# SBM20_counter.net
KiCad netlist of a schematic drawn in EAGLE
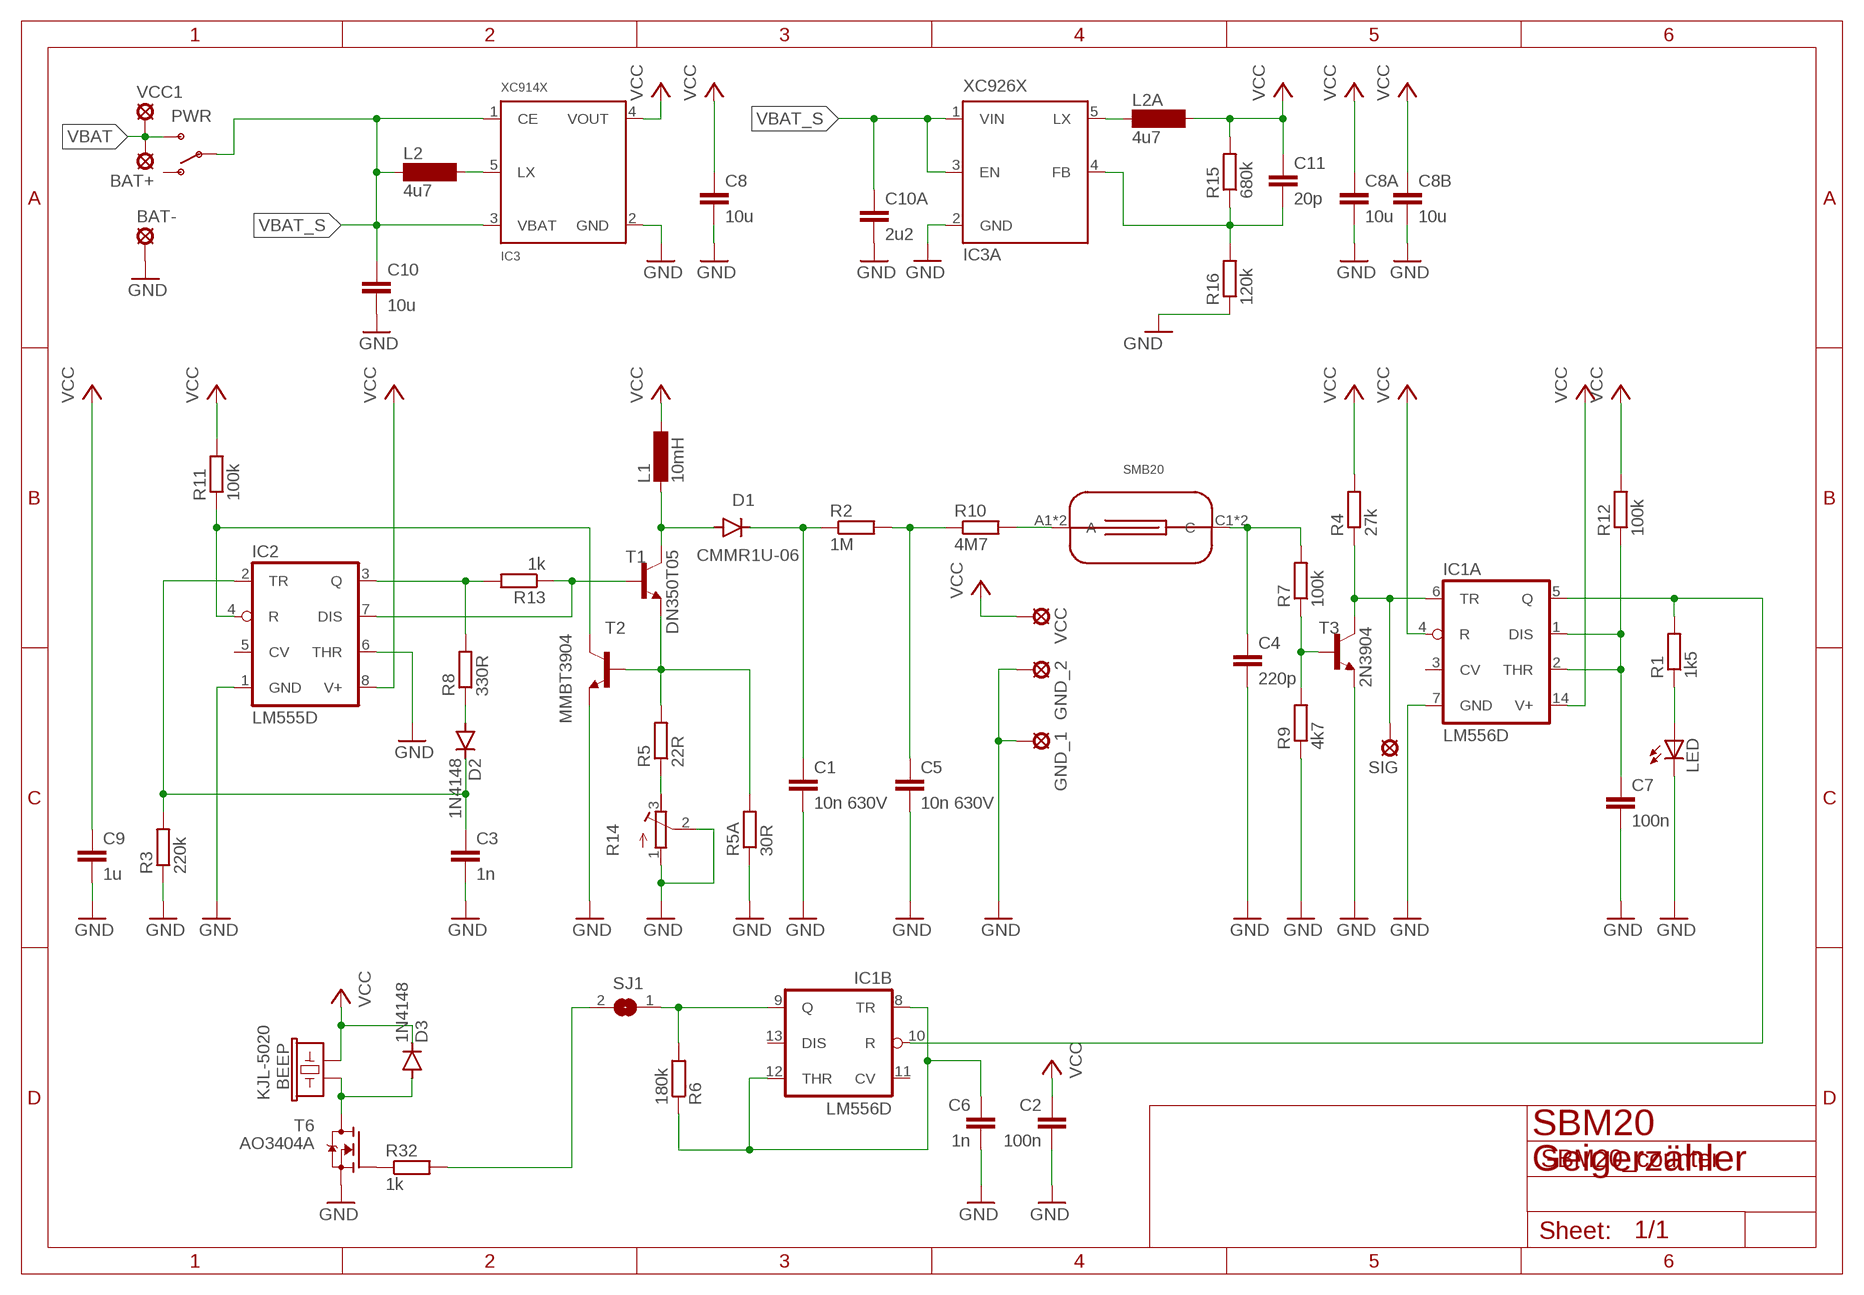
[diagram p0: schematic, sheet 1]

(export (version "E")
  (design (tool "Eeschema 10.0.6"))
  (components
    (comp (ref "BAT+")
      (value "LSP10_CAST")
      (footprint "eagle-import:CASTEL_1")
      (libsource (lib "eagle-import") (part "LSP10_CAST"))
    )
    (comp (ref "BAT-")
      (value "LSP10_CAST")
      (footprint "eagle-import:CASTEL_1")
      (libsource (lib "eagle-import") (part "LSP10_CAST"))
    )
    (comp (ref "BEEP")
      (value "KJL-5020")
      (footprint "eagle-import:KLJ-5020")
      (libsource (lib "eagle-import") (part "BUZZER-5020"))
    )
    (comp (ref "C1")
      (value "10n 630V")
      (footprint "eagle-import:C1206")
      (libsource (lib "eagle-import") (part "C-EUC1206"))
    )
    (comp (ref "C2")
      (value "100n")
      (footprint "eagle-import:C0603")
      (libsource (lib "eagle-import") (part "C-EUC0603"))
    )
    (comp (ref "C3")
      (value "1n")
      (footprint "eagle-import:C0603")
      (libsource (lib "eagle-import") (part "C-EUC0603"))
    )
    (comp (ref "C4")
      (value "220p")
      (footprint "eagle-import:C0603")
      (libsource (lib "eagle-import") (part "C-EUC0603"))
    )
    (comp (ref "C5")
      (value "10n 630V")
      (footprint "eagle-import:C1206")
      (libsource (lib "eagle-import") (part "C-EUC1206"))
    )
    (comp (ref "C6")
      (value "1n")
      (footprint "eagle-import:C0603")
      (libsource (lib "eagle-import") (part "C-EUC0603"))
    )
    (comp (ref "C7")
      (value "100n")
      (footprint "eagle-import:C0603")
      (libsource (lib "eagle-import") (part "C-EUC0603"))
    )
    (comp (ref "C8")
      (value "10u")
      (footprint "eagle-import:C1206")
      (libsource (lib "eagle-import") (part "C-EUC1206"))
    )
    (comp (ref "C8A")
      (value "10u")
      (footprint "eagle-import:C1206")
      (libsource (lib "eagle-import") (part "C-EUC1206"))
    )
    (comp (ref "C8B")
      (value "10u")
      (footprint "eagle-import:C1206")
      (libsource (lib "eagle-import") (part "C-EUC1206"))
    )
    (comp (ref "C9")
      (value "1u")
      (footprint "eagle-import:C1206")
      (libsource (lib "eagle-import") (part "C-EUC1206"))
    )
    (comp (ref "C10")
      (value "10u")
      (footprint "eagle-import:C1206")
      (libsource (lib "eagle-import") (part "C-EUC1206"))
    )
    (comp (ref "C10A")
      (value "2u2")
      (footprint "eagle-import:C1206")
      (libsource (lib "eagle-import") (part "C-EUC1206"))
    )
    (comp (ref "C11")
      (value "20p")
      (footprint "eagle-import:C0603")
      (libsource (lib "eagle-import") (part "C-EUC0603"))
    )
    (comp (ref "D1")
      (value "CMMR1U-06")
      (footprint "eagle-import:DO-214AC")
      (libsource (lib "eagle-import") (part "DIODE-DO-214AC"))
    )
    (comp (ref "D2")
      (value "1N4148")
      (footprint "eagle-import:SOD123")
      (libsource (lib "eagle-import") (part "DIODE-SOD123"))
    )
    (comp (ref "D3")
      (value "1N4148")
      (footprint "eagle-import:SOD123")
      (libsource (lib "eagle-import") (part "DIODE-SOD123"))
    )
    (comp (ref "GND_1")
      (value "LSP10_CAST")
      (footprint "eagle-import:CASTEL_1")
      (libsource (lib "eagle-import") (part "LSP10_CAST"))
    )
    (comp (ref "GND_2")
      (value "LSP10_CAST")
      (footprint "eagle-import:CASTEL_1")
      (libsource (lib "eagle-import") (part "LSP10_CAST"))
    )
    (comp (ref "IC1")
      (value "LM556D")
      (footprint "eagle-import:SO14")
      (libsource (lib "eagle-import") (part "556DLM"))
    )
    (comp (ref "IC2")
      (value "LM555D")
      (footprint "eagle-import:SO08")
      (libsource (lib "eagle-import") (part "555DLM"))
    )
    (comp (ref "IC3")
      (value "XC914X")
      (footprint "eagle-import:SOT23-5")
      (libsource (lib "eagle-import") (part "XC914X"))
    )
    (comp (ref "IC3A")
      (value "XC926X")
      (footprint "eagle-import:SOT23-5")
      (libsource (lib "eagle-import") (part "XC926X"))
    )
    (comp (ref "L1")
      (value "10mH")
      (footprint "eagle-import:L8065")
      (libsource (lib "eagle-import") (part "L-EUL8065"))
    )
    (comp (ref "L2")
      (value "4u7")
      (footprint "eagle-import:L5050")
      (libsource (lib "eagle-import") (part "L"))
    )
    (comp (ref "L2A")
      (value "4u7")
      (footprint "eagle-import:L5050")
      (libsource (lib "eagle-import") (part "L"))
    )
    (comp (ref "LED")
      (value "LEDCHIPLED_1206")
      (footprint "eagle-import:CHIPLED_1206")
      (libsource (lib "eagle-import") (part "LEDCHIPLED_1206"))
    )
    (comp (ref "PWR")
      (value "SWITCH-SPDT-SMD-A")
      (footprint "eagle-import:SWITCH-SPST-SMD-A")
      (libsource (lib "eagle-import") (part "SWITCH-SPDT-SMD-A"))
    )
    (comp (ref "R1")
      (value "1k5")
      (footprint "eagle-import:R0603")
      (libsource (lib "eagle-import") (part "R-EU_R0603"))
    )
    (comp (ref "R2")
      (value "1M")
      (footprint "eagle-import:R1206")
      (libsource (lib "eagle-import") (part "R-EU_R1206"))
    )
    (comp (ref "R3")
      (value "220k")
      (footprint "eagle-import:R0603")
      (libsource (lib "eagle-import") (part "R-EU_R0603"))
    )
    (comp (ref "R4")
      (value "27k")
      (footprint "eagle-import:R0603")
      (libsource (lib "eagle-import") (part "R-EU_R0603"))
    )
    (comp (ref "R5")
      (value "22R")
      (footprint "eagle-import:R0603")
      (libsource (lib "eagle-import") (part "R-EU_R0603"))
    )
    (comp (ref "R5A")
      (value "30R")
      (footprint "eagle-import:R0603")
      (libsource (lib "eagle-import") (part "R-EU_R0603"))
    )
    (comp (ref "R6")
      (value "180k")
      (footprint "eagle-import:R0603")
      (libsource (lib "eagle-import") (part "R-EU_R0603"))
    )
    (comp (ref "R7")
      (value "100k")
      (footprint "eagle-import:R0603")
      (libsource (lib "eagle-import") (part "R-EU_R0603"))
    )
    (comp (ref "R8")
      (value "330R")
      (footprint "eagle-import:R0603")
      (libsource (lib "eagle-import") (part "R-EU_R0603"))
    )
    (comp (ref "R9")
      (value "4k7")
      (footprint "eagle-import:R0603")
      (libsource (lib "eagle-import") (part "R-EU_R0603"))
    )
    (comp (ref "R10")
      (value "4M7")
      (footprint "eagle-import:R1206")
      (libsource (lib "eagle-import") (part "R-EU_R1206"))
    )
    (comp (ref "R11")
      (value "100k")
      (footprint "eagle-import:R0603")
      (libsource (lib "eagle-import") (part "R-EU_R0603"))
    )
    (comp (ref "R12")
      (value "100k")
      (footprint "eagle-import:R0603")
      (libsource (lib "eagle-import") (part "R-EU_R0603"))
    )
    (comp (ref "R13")
      (value "1k")
      (footprint "eagle-import:R0603")
      (libsource (lib "eagle-import") (part "R-EU_R0603"))
    )
    (comp (ref "R14")
      (value "R-TRIMM3224J")
      (footprint "eagle-import:RTRIM3224J")
      (libsource (lib "eagle-import") (part "R-TRIMM3224J"))
    )
    (comp (ref "R15")
      (value "680k")
      (footprint "eagle-import:R0603")
      (libsource (lib "eagle-import") (part "R-EU_R0603"))
    )
    (comp (ref "R16")
      (value "120k")
      (footprint "eagle-import:R0603")
      (libsource (lib "eagle-import") (part "R-EU_R0603"))
    )
    (comp (ref "R32")
      (value "1k")
      (footprint "eagle-import:R0603")
      (libsource (lib "eagle-import") (part "R-EU_R0603"))
    )
    (comp (ref "SIG")
      (value "LSP10_CAST")
      (footprint "eagle-import:CASTEL_1")
      (libsource (lib "eagle-import") (part "LSP10_CAST"))
    )
    (comp (ref "SJ1") (value "SJ") (footprint "eagle-import:SJ") (libsource (lib "eagle-import") (part "SJ")))
    (comp (ref "T1")
      (value "DN350T05")
      (footprint "eagle-import:SOT23-BEC")
      (libsource (lib "eagle-import") (part "-NPN-SOT23-BECMMBT3904LT1"))
    )
    (comp (ref "T2")
      (value "MMBT3904")
      (footprint "eagle-import:SOT23-BEC")
      (libsource (lib "eagle-import") (part "-NPN-SOT23-BECMMBT3904LT1"))
    )
    (comp (ref "T3")
      (value "2N3904")
      (footprint "eagle-import:SOT23-BEC")
      (libsource (lib "eagle-import") (part "-NPN-SOT23-BECMMBT3904LT1"))
    )
    (comp (ref "T6")
      (value "AO3404A")
      (footprint "eagle-import:SOT23")
      (libsource (lib "eagle-import") (part "N-MOSFET-SOT23-3"))
    )
    (comp (ref "U$1")
      (value "SMB20")
      (footprint "eagle-import:STS5")
      (libsource (lib "eagle-import") (part "STS5"))
    )
    (comp (ref "VCC")
      (value "LSP10_CAST")
      (footprint "eagle-import:CASTEL_1")
      (libsource (lib "eagle-import") (part "LSP10_CAST"))
    )
    (comp (ref "VCC1")
      (value "LSP10_CAST")
      (footprint "eagle-import:CASTEL_1")
      (libsource (lib "eagle-import") (part "LSP10_CAST"))
    )
  )
  (nets
    (net (code "1") (name "GND") (class "Default")
      (node (ref "BAT-") (pin "C") (pinfunction "MP_C") (pintype "passive"))
      (node (ref "BAT-") (pin "V") (pinfunction "MP_V") (pintype "passive"))
      (node (ref "C1") (pin "2") (pinfunction "2_2") (pintype "passive"))
      (node (ref "C10") (pin "2") (pinfunction "2_2") (pintype "passive"))
      (node (ref "C10A") (pin "2") (pinfunction "2_2") (pintype "passive"))
      (node (ref "C2") (pin "2") (pinfunction "2_2") (pintype "passive"))
      (node (ref "C3") (pin "2") (pinfunction "2_2") (pintype "passive"))
      (node (ref "C4") (pin "2") (pinfunction "2_2") (pintype "passive"))
      (node (ref "C5") (pin "2") (pinfunction "2_2") (pintype "passive"))
      (node (ref "C6") (pin "2") (pinfunction "2_2") (pintype "passive"))
      (node (ref "C7") (pin "2") (pinfunction "2_2") (pintype "passive"))
      (node (ref "C8") (pin "2") (pinfunction "2_2") (pintype "passive"))
      (node (ref "C8A") (pin "2") (pinfunction "2_2") (pintype "passive"))
      (node (ref "C8B") (pin "2") (pinfunction "2_2") (pintype "passive"))
      (node (ref "C9") (pin "2") (pinfunction "2_2") (pintype "passive"))
      (node (ref "GND_1") (pin "C") (pinfunction "MP_C") (pintype "passive"))
      (node (ref "GND_1") (pin "V") (pinfunction "MP_V") (pintype "passive"))
      (node (ref "GND_2") (pin "C") (pinfunction "MP_C") (pintype "passive"))
      (node (ref "GND_2") (pin "V") (pinfunction "MP_V") (pintype "passive"))
      (node (ref "IC1") (pin "7") (pinfunction "GND_7") (pintype "power_in"))
      (node (ref "IC2") (pin "1") (pinfunction "GND_1") (pintype "power_in"))
      (node (ref "IC2") (pin "6") (pinfunction "THR_6") (pintype "input"))
      (node (ref "IC3") (pin "2") (pinfunction "GND_2") (pintype "power_in"))
      (node (ref "IC3A") (pin "2") (pinfunction "GND_2") (pintype "power_in"))
      (node (ref "LED") (pin "C") (pinfunction "C_C") (pintype "passive"))
      (node (ref "R14") (pin "1") (pinfunction "A_1") (pintype "passive"))
      (node (ref "R14") (pin "2") (pinfunction "S_2") (pintype "passive"))
      (node (ref "R16") (pin "1") (pinfunction "1_1") (pintype "passive"))
      (node (ref "R3") (pin "1") (pinfunction "1_1") (pintype "passive"))
      (node (ref "R5A") (pin "1") (pinfunction "1_1") (pintype "passive"))
      (node (ref "R9") (pin "1") (pinfunction "1_1") (pintype "passive"))
      (node (ref "T2") (pin "E") (pinfunction "E_E") (pintype "passive"))
      (node (ref "T3") (pin "E") (pinfunction "E_E") (pintype "passive"))
      (node (ref "T6") (pin "2") (pinfunction "S_2") (pintype "passive"))
    )
    (net (code "2") (name "Net-(BEEP-2)") (class "Default")
      (node (ref "BEEP") (pin "-") (pinfunction "2_-") (pintype "passive"))
      (node (ref "D3") (pin "A") (pinfunction "A_A") (pintype "passive"))
      (node (ref "T6") (pin "3") (pinfunction "D_3") (pintype "passive"))
    )
    (net (code "3") (name "Net-(C1-Pad1)") (class "Default")
      (node (ref "C1") (pin "1") (pinfunction "1_1") (pintype "passive"))
      (node (ref "D1") (pin "C") (pinfunction "C_C") (pintype "passive"))
      (node (ref "R2") (pin "1") (pinfunction "1_1") (pintype "passive"))
    )
    (net (code "4") (name "Net-(C4-Pad1)") (class "Default")
      (node (ref "C4") (pin "1") (pinfunction "1_1") (pintype "passive"))
      (node (ref "R7") (pin "2") (pinfunction "2_2") (pintype "passive"))
      (node (ref "U$1") (pin "C1") (pinfunction "C_C1") (pintype "passive"))
      (node (ref "U$1") (pin "C2") (pinfunction "C_C2") (pintype "passive"))
    )
    (net (code "5") (name "Net-(C5-Pad1)") (class "Default")
      (node (ref "C5") (pin "1") (pinfunction "1_1") (pintype "passive"))
      (node (ref "R10") (pin "1") (pinfunction "1_1") (pintype "passive"))
      (node (ref "R2") (pin "2") (pinfunction "2_2") (pintype "passive"))
    )
    (net (code "6") (name "Net-(D1-PadA)") (class "Default")
      (node (ref "D1") (pin "A") (pinfunction "A_A") (pintype "passive"))
      (node (ref "L1") (pin "2") (pinfunction "2_2") (pintype "passive"))
      (node (ref "T1") (pin "C") (pinfunction "C_C") (pintype "passive"))
    )
    (net (code "7") (name "Net-(D2-PadA)") (class "Default")
      (node (ref "D2") (pin "A") (pinfunction "A_A") (pintype "passive"))
      (node (ref "R8") (pin "1") (pinfunction "1_1") (pintype "passive"))
    )
    (net (code "8") (name "Net-(IC1A-DIS)") (class "Default")
      (node (ref "C7") (pin "1") (pinfunction "1_1") (pintype "passive"))
      (node (ref "IC1") (pin "1") (pinfunction "DIS_1") (pintype "input"))
      (node (ref "IC1") (pin "2") (pinfunction "THR_2") (pintype "input"))
      (node (ref "R12") (pin "1") (pinfunction "1_1") (pintype "passive"))
    )
    (net (code "9") (name "Net-(IC1A-Q)") (class "Default")
      (node (ref "IC1") (pin "10") (pinfunction "R_10") (pintype "input"))
      (node (ref "IC1") (pin "5") (pinfunction "Q_5") (pintype "output"))
      (node (ref "R1") (pin "2") (pinfunction "2_2") (pintype "passive"))
    )
    (net (code "10") (name "Net-(IC1A-TR)") (class "Default")
      (node (ref "IC1") (pin "6") (pinfunction "TR_6") (pintype "input"))
      (node (ref "R4") (pin "1") (pinfunction "1_1") (pintype "passive"))
      (node (ref "SIG") (pin "C") (pinfunction "MP_C") (pintype "passive"))
      (node (ref "SIG") (pin "V") (pinfunction "MP_V") (pintype "passive"))
      (node (ref "T3") (pin "C") (pinfunction "C_C") (pintype "passive"))
    )
    (net (code "11") (name "Net-(IC1B-Q)") (class "Default")
      (node (ref "IC1") (pin "9") (pinfunction "Q_9") (pintype "output"))
      (node (ref "R6") (pin "2") (pinfunction "2_2") (pintype "passive"))
      (node (ref "SJ1") (pin "1") (pinfunction "1_1") (pintype "passive"))
    )
    (net (code "12") (name "Net-(IC1B-THR)") (class "Default")
      (node (ref "C6") (pin "1") (pinfunction "1_1") (pintype "passive"))
      (node (ref "IC1") (pin "12") (pinfunction "THR_12") (pintype "input"))
      (node (ref "IC1") (pin "8") (pinfunction "TR_8") (pintype "input"))
      (node (ref "R6") (pin "1") (pinfunction "1_1") (pintype "passive"))
    )
    (net (code "13") (name "Net-(IC2-DIS)") (class "Default")
      (node (ref "IC2") (pin "7") (pinfunction "DIS_7") (pintype "input"))
      (node (ref "R13") (pin "1") (pinfunction "1_1") (pintype "passive"))
      (node (ref "T1") (pin "B") (pinfunction "B_B") (pintype "passive"))
    )
    (net (code "14") (name "Net-(IC2-Q)") (class "Default")
      (node (ref "IC2") (pin "3") (pinfunction "Q_3") (pintype "output"))
      (node (ref "R13") (pin "2") (pinfunction "2_2") (pintype "passive"))
      (node (ref "R8") (pin "2") (pinfunction "2_2") (pintype "passive"))
    )
    (net (code "15") (name "Net-(IC2-R)") (class "Default")
      (node (ref "IC2") (pin "4") (pinfunction "R_4") (pintype "input"))
      (node (ref "R11") (pin "1") (pinfunction "1_1") (pintype "passive"))
      (node (ref "T2") (pin "C") (pinfunction "C_C") (pintype "passive"))
    )
    (net (code "16") (name "Net-(IC2-TR)") (class "Default")
      (node (ref "C3") (pin "1") (pinfunction "1_1") (pintype "passive"))
      (node (ref "D2") (pin "C") (pinfunction "C_C") (pintype "passive"))
      (node (ref "IC2") (pin "2") (pinfunction "TR_2") (pintype "input"))
      (node (ref "R3") (pin "2") (pinfunction "2_2") (pintype "passive"))
    )
    (net (code "17") (name "Net-(IC3-LX)") (class "Default")
      (node (ref "IC3") (pin "5") (pinfunction "LX_5") (pintype "passive"))
      (node (ref "L2") (pin "2") (pinfunction "2_2") (pintype "passive"))
    )
    (net (code "18") (name "Net-(IC3A-FB)") (class "Default")
      (node (ref "C11") (pin "2") (pinfunction "2_2") (pintype "passive"))
      (node (ref "IC3A") (pin "4") (pinfunction "FB_4") (pintype "passive"))
      (node (ref "R15") (pin "1") (pinfunction "1_1") (pintype "passive"))
      (node (ref "R16") (pin "2") (pinfunction "2_2") (pintype "passive"))
    )
    (net (code "19") (name "Net-(IC3A-LX)") (class "Default")
      (node (ref "IC3A") (pin "5") (pinfunction "LX_5") (pintype "passive"))
      (node (ref "L2A") (pin "1") (pinfunction "1_1") (pintype "passive"))
    )
    (net (code "20") (name "Net-(LED-PadA)") (class "Default")
      (node (ref "LED") (pin "A") (pinfunction "A_A") (pintype "passive"))
      (node (ref "R1") (pin "1") (pinfunction "1_1") (pintype "passive"))
    )
    (net (code "21") (name "Net-(R5-Pad2)") (class "Default")
      (node (ref "R5") (pin "2") (pinfunction "2_2") (pintype "passive"))
      (node (ref "R5A") (pin "2") (pinfunction "2_2") (pintype "passive"))
      (node (ref "T1") (pin "E") (pinfunction "E_E") (pintype "passive"))
      (node (ref "T2") (pin "B") (pinfunction "B_B") (pintype "passive"))
    )
    (net (code "22") (name "Net-(R7-Pad1)") (class "Default")
      (node (ref "R7") (pin "1") (pinfunction "1_1") (pintype "passive"))
      (node (ref "R9") (pin "2") (pinfunction "2_2") (pintype "passive"))
      (node (ref "T3") (pin "B") (pinfunction "B_B") (pintype "passive"))
    )
    (net (code "23") (name "Net-(R10-Pad2)") (class "Default")
      (node (ref "R10") (pin "2") (pinfunction "2_2") (pintype "passive"))
      (node (ref "U$1") (pin "A1") (pinfunction "A_A1") (pintype "passive"))
      (node (ref "U$1") (pin "A2") (pinfunction "A_A2") (pintype "passive"))
    )
    (net (code "24") (name "Net-(R14-E)") (class "Default")
      (node (ref "R14") (pin "3") (pinfunction "E_3") (pintype "passive"))
      (node (ref "R5") (pin "1") (pinfunction "1_1") (pintype "passive"))
    )
    (net (code "25") (name "Net-(R32-Pad2)") (class "Default")
      (node (ref "R32") (pin "2") (pinfunction "2_2") (pintype "passive"))
      (node (ref "SJ1") (pin "2") (pinfunction "2_2") (pintype "passive"))
    )
    (net (code "26") (name "Net-(T6-G)") (class "Default")
      (node (ref "R32") (pin "1") (pinfunction "1_1") (pintype "passive"))
      (node (ref "T6") (pin "1") (pinfunction "G_1") (pintype "passive"))
    )
    (net (code "27") (name "VBAT") (class "Default")
      (node (ref "BAT+") (pin "C") (pinfunction "MP_C") (pintype "passive"))
      (node (ref "BAT+") (pin "V") (pinfunction "MP_V") (pintype "passive"))
      (node (ref "PWR") (pin "3") (pinfunction "S_3") (pintype "passive"))
      (node (ref "VCC1") (pin "C") (pinfunction "MP_C") (pintype "passive"))
      (node (ref "VCC1") (pin "V") (pinfunction "MP_V") (pintype "passive"))
    )
    (net (code "28") (name "VBAT_S") (class "Default")
      (node (ref "C10") (pin "1") (pinfunction "1_1") (pintype "passive"))
      (node (ref "C10A") (pin "1") (pinfunction "1_1") (pintype "passive"))
      (node (ref "IC3") (pin "1") (pinfunction "CE_1") (pintype "input"))
      (node (ref "IC3") (pin "3") (pinfunction "VBAT_3") (pintype "power_in"))
      (node (ref "IC3A") (pin "1") (pinfunction "VIN_1") (pintype "power_in"))
      (node (ref "IC3A") (pin "3") (pinfunction "EN_3") (pintype "input"))
      (node (ref "L2") (pin "1") (pinfunction "1_1") (pintype "passive"))
      (node (ref "PWR") (pin "2") (pinfunction "P_2") (pintype "passive"))
    )
    (net (code "29") (name "VCC") (class "Default")
      (node (ref "BEEP") (pin "+") (pinfunction "1_+") (pintype "passive"))
      (node (ref "C11") (pin "1") (pinfunction "1_1") (pintype "passive"))
      (node (ref "C2") (pin "1") (pinfunction "1_1") (pintype "passive"))
      (node (ref "C8") (pin "1") (pinfunction "1_1") (pintype "passive"))
      (node (ref "C8A") (pin "1") (pinfunction "1_1") (pintype "passive"))
      (node (ref "C8B") (pin "1") (pinfunction "1_1") (pintype "passive"))
      (node (ref "C9") (pin "1") (pinfunction "1_1") (pintype "passive"))
      (node (ref "D3") (pin "C") (pinfunction "C_C") (pintype "passive"))
      (node (ref "IC1") (pin "14") (pinfunction "V+_14") (pintype "power_in"))
      (node (ref "IC1") (pin "4") (pinfunction "R_4") (pintype "input"))
      (node (ref "IC2") (pin "8") (pinfunction "V+_8") (pintype "power_in"))
      (node (ref "IC3") (pin "4") (pinfunction "VOUT_4") (pintype "power_in"))
      (node (ref "L1") (pin "1") (pinfunction "1_1") (pintype "passive"))
      (node (ref "L2A") (pin "2") (pinfunction "2_2") (pintype "passive"))
      (node (ref "R11") (pin "2") (pinfunction "2_2") (pintype "passive"))
      (node (ref "R12") (pin "2") (pinfunction "2_2") (pintype "passive"))
      (node (ref "R15") (pin "2") (pinfunction "2_2") (pintype "passive"))
      (node (ref "R4") (pin "2") (pinfunction "2_2") (pintype "passive"))
      (node (ref "VCC") (pin "C") (pinfunction "MP_C") (pintype "passive"))
      (node (ref "VCC") (pin "V") (pinfunction "MP_V") (pintype "passive"))
    )
    (net (code "30") (name "unconnected-(IC1A-CV-Pad3)") (class "Default")
      (node (ref "IC1") (pin "3") (pinfunction "CV_3") (pintype "input"))
    )
    (net (code "31") (name "unconnected-(IC1B-CV-Pad11)") (class "Default")
      (node (ref "IC1") (pin "11") (pinfunction "CV_11") (pintype "input"))
    )
    (net (code "32") (name "unconnected-(IC1B-DIS-Pad13)") (class "Default")
      (node (ref "IC1") (pin "13") (pinfunction "DIS_13") (pintype "input"))
    )
    (net (code "33") (name "unconnected-(IC2-CV-Pad5)") (class "Default")
      (node (ref "IC2") (pin "5") (pinfunction "CV_5") (pintype "input"))
    )
    (net (code "34") (name "unconnected-(PWR-O-Pad1)") (class "Default")
      (node (ref "PWR") (pin "1") (pinfunction "O_1") (pintype "passive"))
    )
  )
)
